# TdsReworkfullSMD.net
KiCad netlist of a schematic drawn in EAGLE
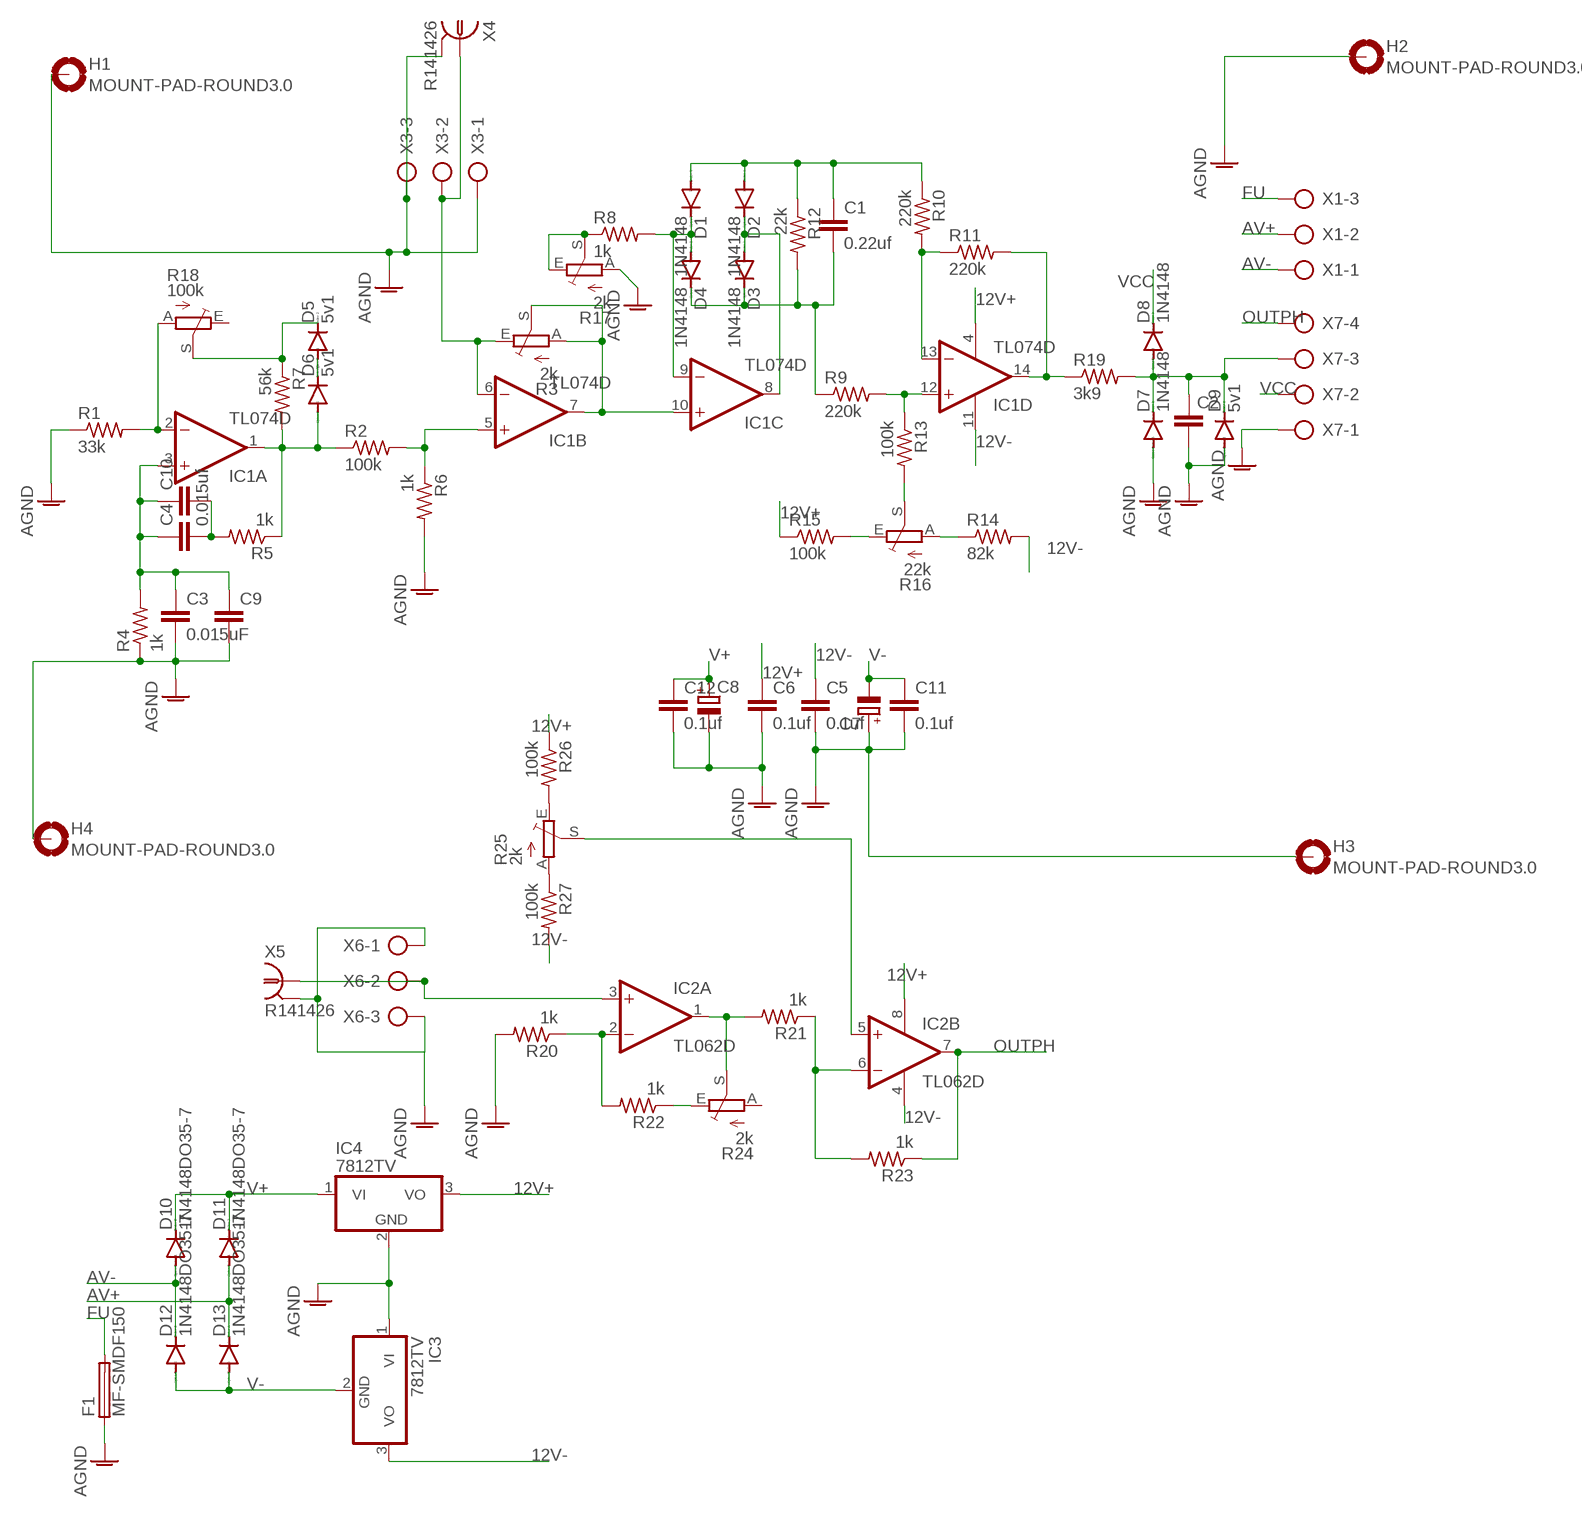
[diagram p0: schematic, sheet 1]

(export (version "E")
  (design (tool "Eeschema 10.0.6"))
  (components
    (comp (ref "C1")
      (value "0.22uf")
      (footprint "eagle-import:C0805")
      (libsource (lib "eagle-import") (part "C-EUC0805"))
    )
    (comp (ref "C2")
      (value "C-EUC0805")
      (footprint "eagle-import:C0805")
      (libsource (lib "eagle-import") (part "C-EUC0805"))
    )
    (comp (ref "C3")
      (value "0.015uF")
      (footprint "eagle-import:C050-024X044")
      (libsource (lib "eagle-import") (part "C-EU050-024X044"))
    )
    (comp (ref "C4")
      (value "0.015uf")
      (footprint "eagle-import:C050-024X044")
      (libsource (lib "eagle-import") (part "C-EU050-024X044"))
    )
    (comp (ref "C5")
      (value "0.1uf")
      (footprint "eagle-import:C0805")
      (libsource (lib "eagle-import") (part "C-EUC0805"))
    )
    (comp (ref "C6")
      (value "0.1uf")
      (footprint "eagle-import:C0805")
      (libsource (lib "eagle-import") (part "C-EUC0805"))
    )
    (comp (ref "C7")
      (value "CPOL-EUE5-8.5")
      (footprint "eagle-import:E5-8,5")
      (libsource (lib "eagle-import") (part "CPOL-EUE5-8.5"))
    )
    (comp (ref "C8")
      (value "CPOL-EUE5-8.5")
      (footprint "eagle-import:E5-8,5")
      (libsource (lib "eagle-import") (part "CPOL-EUE5-8.5"))
    )
    (comp (ref "C9")
      (value "C-EUC0805")
      (footprint "eagle-import:C0805")
      (libsource (lib "eagle-import") (part "C-EUC0805"))
    )
    (comp (ref "C10")
      (value "C-EUC0805")
      (footprint "eagle-import:C0805")
      (libsource (lib "eagle-import") (part "C-EUC0805"))
    )
    (comp (ref "C11")
      (value "0.1uf")
      (footprint "eagle-import:C0805")
      (libsource (lib "eagle-import") (part "C-EUC0805"))
    )
    (comp (ref "C12")
      (value "0.1uf")
      (footprint "eagle-import:C0805")
      (libsource (lib "eagle-import") (part "C-EUC0805"))
    )
    (comp (ref "D1")
      (value "1N4148")
      (footprint "eagle-import:DO35-7")
      (libsource (lib "eagle-import") (part "1N4148DO35-7"))
    )
    (comp (ref "D2")
      (value "1N4148")
      (footprint "eagle-import:DO35-7")
      (libsource (lib "eagle-import") (part "1N4148DO35-7"))
    )
    (comp (ref "D3")
      (value "1N4148")
      (footprint "eagle-import:DO35-7")
      (libsource (lib "eagle-import") (part "1N4148DO35-7"))
    )
    (comp (ref "D4")
      (value "1N4148")
      (footprint "eagle-import:DO35-7")
      (libsource (lib "eagle-import") (part "1N4148DO35-7"))
    )
    (comp (ref "D5")
      (value "5v1")
      (footprint "eagle-import:DO35-7")
      (libsource (lib "eagle-import") (part "1N4148DO35-7"))
    )
    (comp (ref "D6")
      (value "5v1")
      (footprint "eagle-import:DO35-7")
      (libsource (lib "eagle-import") (part "1N4148DO35-7"))
    )
    (comp (ref "D7")
      (value "1N4148")
      (footprint "eagle-import:DO35-7")
      (libsource (lib "eagle-import") (part "1N4148DO35-7"))
    )
    (comp (ref "D8")
      (value "1N4148")
      (footprint "eagle-import:DO35-7")
      (libsource (lib "eagle-import") (part "1N4148DO35-7"))
    )
    (comp (ref "D9")
      (value "5v1")
      (footprint "eagle-import:DO35-7")
      (libsource (lib "eagle-import") (part "1N4148DO35-7"))
    )
    (comp (ref "D10")
      (value "1N4148DO35-7")
      (footprint "eagle-import:DO35-7")
      (libsource (lib "eagle-import") (part "1N4148DO35-7"))
    )
    (comp (ref "D11")
      (value "1N4148DO35-7")
      (footprint "eagle-import:DO35-7")
      (libsource (lib "eagle-import") (part "1N4148DO35-7"))
    )
    (comp (ref "D12")
      (value "1N4148DO35-7")
      (footprint "eagle-import:DO35-7")
      (libsource (lib "eagle-import") (part "1N4148DO35-7"))
    )
    (comp (ref "D13")
      (value "1N4148DO35-7")
      (footprint "eagle-import:DO35-7")
      (libsource (lib "eagle-import") (part "1N4148DO35-7"))
    )
    (comp (ref "F1")
      (value "MF-SMDF150")
      (footprint "eagle-import:MF-SMDF050")
      (libsource (lib "eagle-import") (part "MF-SMDF150"))
    )
    (comp (ref "H1")
      (value "MOUNT-PAD-ROUND3.0")
      (footprint "eagle-import:3,0-PAD")
      (libsource (lib "eagle-import") (part "MOUNT-PAD-ROUND3.0"))
    )
    (comp (ref "H2")
      (value "MOUNT-PAD-ROUND3.0")
      (footprint "eagle-import:3,0-PAD")
      (libsource (lib "eagle-import") (part "MOUNT-PAD-ROUND3.0"))
    )
    (comp (ref "H3")
      (value "MOUNT-PAD-ROUND3.0")
      (footprint "eagle-import:3,0-PAD")
      (libsource (lib "eagle-import") (part "MOUNT-PAD-ROUND3.0"))
    )
    (comp (ref "H4")
      (value "MOUNT-PAD-ROUND3.0")
      (footprint "eagle-import:3,0-PAD")
      (libsource (lib "eagle-import") (part "MOUNT-PAD-ROUND3.0"))
    )
    (comp (ref "IC1")
      (value "TL074D")
      (footprint "eagle-import:SO14")
      (libsource (lib "eagle-import") (part "TL074D"))
    )
    (comp (ref "IC2")
      (value "TL062D")
      (footprint "eagle-import:SO08")
      (libsource (lib "eagle-import") (part "TL062D"))
    )
    (comp (ref "IC3")
      (value "7812TV")
      (footprint "eagle-import:TO220V")
      (libsource (lib "eagle-import") (part "78TV12"))
    )
    (comp (ref "IC4")
      (value "7812TV")
      (footprint "eagle-import:TO220V")
      (libsource (lib "eagle-import") (part "78TV12"))
    )
    (comp (ref "R1")
      (value "33k")
      (footprint "eagle-import:R0805")
      (libsource (lib "eagle-import") (part "R-US_R0805"))
    )
    (comp (ref "R2")
      (value "100k")
      (footprint "eagle-import:R0805")
      (libsource (lib "eagle-import") (part "R-US_R0805"))
    )
    (comp (ref "R3")
      (value "2k")
      (footprint "eagle-import:S64W")
      (libsource (lib "eagle-import") (part "TRIM_EU-S64W"))
    )
    (comp (ref "R4")
      (value "1k")
      (footprint "eagle-import:R0805")
      (libsource (lib "eagle-import") (part "R-US_R0805"))
    )
    (comp (ref "R5")
      (value "1k")
      (footprint "eagle-import:R0805")
      (libsource (lib "eagle-import") (part "R-US_R0805"))
    )
    (comp (ref "R6")
      (value "1k")
      (footprint "eagle-import:R0805")
      (libsource (lib "eagle-import") (part "R-US_R0805"))
    )
    (comp (ref "R7")
      (value "56k")
      (footprint "eagle-import:R0805")
      (libsource (lib "eagle-import") (part "R-US_R0805"))
    )
    (comp (ref "R8")
      (value "1k")
      (footprint "eagle-import:R0805")
      (libsource (lib "eagle-import") (part "R-US_R0805"))
    )
    (comp (ref "R9")
      (value "220k")
      (footprint "eagle-import:R0805")
      (libsource (lib "eagle-import") (part "R-US_R0805"))
    )
    (comp (ref "R10")
      (value "220k")
      (footprint "eagle-import:R0805")
      (libsource (lib "eagle-import") (part "R-US_R0805"))
    )
    (comp (ref "R11")
      (value "220k")
      (footprint "eagle-import:R0805")
      (libsource (lib "eagle-import") (part "R-US_R0805"))
    )
    (comp (ref "R12")
      (value "22k")
      (footprint "eagle-import:R0805")
      (libsource (lib "eagle-import") (part "R-US_R0805"))
    )
    (comp (ref "R13")
      (value "100k")
      (footprint "eagle-import:R0805")
      (libsource (lib "eagle-import") (part "R-US_R0805"))
    )
    (comp (ref "R14")
      (value "82k")
      (footprint "eagle-import:R0805")
      (libsource (lib "eagle-import") (part "R-US_R0805"))
    )
    (comp (ref "R15")
      (value "100k")
      (footprint "eagle-import:R0805")
      (libsource (lib "eagle-import") (part "R-US_R0805"))
    )
    (comp (ref "R16")
      (value "22k")
      (footprint "eagle-import:S64W")
      (libsource (lib "eagle-import") (part "TRIM_EU-S64W"))
    )
    (comp (ref "R17")
      (value "2k")
      (footprint "eagle-import:S64W")
      (libsource (lib "eagle-import") (part "TRIM_EU-S64W"))
    )
    (comp (ref "R18")
      (value "100k")
      (footprint "eagle-import:S64W")
      (libsource (lib "eagle-import") (part "TRIM_EU-S64W"))
    )
    (comp (ref "R19")
      (value "3k9")
      (footprint "eagle-import:R0805")
      (libsource (lib "eagle-import") (part "R-US_R0805"))
    )
    (comp (ref "R20")
      (value "1k")
      (footprint "eagle-import:R0805")
      (libsource (lib "eagle-import") (part "R-US_R0805"))
    )
    (comp (ref "R21")
      (value "1k")
      (footprint "eagle-import:R0805")
      (libsource (lib "eagle-import") (part "R-US_R0805"))
    )
    (comp (ref "R22")
      (value "1k")
      (footprint "eagle-import:R0805")
      (libsource (lib "eagle-import") (part "R-US_R0805"))
    )
    (comp (ref "R23")
      (value "1k")
      (footprint "eagle-import:R0805")
      (libsource (lib "eagle-import") (part "R-US_R0805"))
    )
    (comp (ref "R24")
      (value "2k")
      (footprint "eagle-import:S64W")
      (libsource (lib "eagle-import") (part "TRIM_EU-S64W"))
    )
    (comp (ref "R25")
      (value "2k")
      (footprint "eagle-import:S64W")
      (libsource (lib "eagle-import") (part "TRIM_EU-S64W"))
    )
    (comp (ref "R26")
      (value "100k")
      (footprint "eagle-import:R0805")
      (libsource (lib "eagle-import") (part "R-US_R0805"))
    )
    (comp (ref "R27")
      (value "100k")
      (footprint "eagle-import:R0805")
      (libsource (lib "eagle-import") (part "R-US_R0805"))
    )
    (comp (ref "X1")
      (value "AK500/3")
      (footprint "eagle-import:AK500_3")
      (libsource (lib "eagle-import") (part "AK500/3"))
    )
    (comp (ref "X3")
      (value "AK500/3")
      (footprint "eagle-import:AK500_3")
      (libsource (lib "eagle-import") (part "AK500/3"))
    )
    (comp (ref "X4")
      (value "R141426")
      (footprint "eagle-import:R141426")
      (fields (field (name "MF") "FARNELL") (field (name "MPN") "R141426161"))
      (libsource (lib "eagle-import") (part "R141426"))
    )
    (comp (ref "X5")
      (value "R141426")
      (footprint "eagle-import:R141426")
      (fields (field (name "MF") "FARNELL") (field (name "MPN") "R141426161"))
      (libsource (lib "eagle-import") (part "R141426"))
    )
    (comp (ref "X6")
      (value "AK500/3")
      (footprint "eagle-import:AK500_3")
      (libsource (lib "eagle-import") (part "AK500/3"))
    )
    (comp (ref "X7")
      (value "AK500/4")
      (footprint "eagle-import:AK500_4")
      (libsource (lib "eagle-import") (part "AK500/4"))
    )
  )
  (nets
    (net (code "1") (name "/12V+") (class "Default")
      (node (ref "C6") (pin "1") (pinfunction "1_1") (pintype "passive"))
      (node (ref "IC1") (pin "4") (pinfunction "V+_4") (pintype "power_in"))
      (node (ref "IC2") (pin "8") (pinfunction "V+_8") (pintype "power_in"))
      (node (ref "IC4") (pin "3") (pinfunction "VO_3") (pintype "passive"))
      (node (ref "R15") (pin "1") (pinfunction "1_1") (pintype "passive"))
      (node (ref "R26") (pin "1") (pinfunction "1_1") (pintype "passive"))
    )
    (net (code "2") (name "/12V-") (class "Default")
      (node (ref "C5") (pin "1") (pinfunction "1_1") (pintype "passive"))
      (node (ref "IC1") (pin "11") (pinfunction "V-_11") (pintype "power_in"))
      (node (ref "IC2") (pin "4") (pinfunction "V-_4") (pintype "power_in"))
      (node (ref "IC3") (pin "3") (pinfunction "VO_3") (pintype "passive"))
      (node (ref "R14") (pin "2") (pinfunction "2_2") (pintype "passive"))
      (node (ref "R27") (pin "2") (pinfunction "2_2") (pintype "passive"))
    )
    (net (code "3") (name "/AV+") (class "Default")
      (node (ref "D11") (pin "A") (pinfunction "A_A") (pintype "passive"))
      (node (ref "D13") (pin "C") (pinfunction "C_C") (pintype "passive"))
      (node (ref "X1") (pin "2") (pinfunction "KL_2") (pintype "passive"))
    )
    (net (code "4") (name "/AV-") (class "Default")
      (node (ref "D10") (pin "A") (pinfunction "A_A") (pintype "passive"))
      (node (ref "D12") (pin "C") (pinfunction "C_C") (pintype "passive"))
      (node (ref "X1") (pin "1") (pinfunction "KL_1") (pintype "passive"))
    )
    (net (code "5") (name "/FU") (class "Default")
      (node (ref "F1") (pin "2") (pinfunction "2_2") (pintype "passive"))
      (node (ref "X1") (pin "3") (pinfunction "KL_3") (pintype "passive"))
    )
    (net (code "6") (name "/OUTPH") (class "Default")
      (node (ref "IC2") (pin "7") (pinfunction "OUT_7") (pintype "output"))
      (node (ref "R23") (pin "1") (pinfunction "1_1") (pintype "passive"))
      (node (ref "X7") (pin "4") (pinfunction "KL_4") (pintype "passive"))
    )
    (net (code "7") (name "/V+") (class "Default")
      (node (ref "C12") (pin "1") (pinfunction "1_1") (pintype "passive"))
      (node (ref "C8") (pin "+") (pinfunction "+_+") (pintype "passive"))
      (node (ref "D10") (pin "C") (pinfunction "C_C") (pintype "passive"))
      (node (ref "D11") (pin "C") (pinfunction "C_C") (pintype "passive"))
      (node (ref "IC4") (pin "1") (pinfunction "VI_1") (pintype "input"))
    )
    (net (code "8") (name "/V-") (class "Default")
      (node (ref "C11") (pin "1") (pinfunction "1_1") (pintype "passive"))
      (node (ref "C7") (pin "-") (pinfunction "-_-") (pintype "passive"))
      (node (ref "D12") (pin "A") (pinfunction "A_A") (pintype "passive"))
      (node (ref "D13") (pin "A") (pinfunction "A_A") (pintype "passive"))
      (node (ref "IC3") (pin "2") (pinfunction "GND_2") (pintype "passive"))
    )
    (net (code "9") (name "/VCC") (class "Default")
      (node (ref "D8") (pin "C") (pinfunction "C_C") (pintype "passive"))
      (node (ref "X7") (pin "2") (pinfunction "KL_2") (pintype "passive"))
    )
    (net (code "10") (name "AGND") (class "Default")
      (node (ref "C11") (pin "2") (pinfunction "2_2") (pintype "passive"))
      (node (ref "C12") (pin "2") (pinfunction "2_2") (pintype "passive"))
      (node (ref "C2") (pin "2") (pinfunction "2_2") (pintype "passive"))
      (node (ref "C3") (pin "2") (pinfunction "2_2") (pintype "passive"))
      (node (ref "C5") (pin "2") (pinfunction "2_2") (pintype "passive"))
      (node (ref "C6") (pin "2") (pinfunction "2_2") (pintype "passive"))
      (node (ref "C7") (pin "+") (pinfunction "+_+") (pintype "passive"))
      (node (ref "C8") (pin "-") (pinfunction "-_-") (pintype "passive"))
      (node (ref "C9") (pin "2") (pinfunction "2_2") (pintype "passive"))
      (node (ref "D7") (pin "A") (pinfunction "A_A") (pintype "passive"))
      (node (ref "D9") (pin "A") (pinfunction "A_A") (pintype "passive"))
      (node (ref "F1") (pin "1") (pinfunction "1_1") (pintype "passive"))
      (node (ref "H1") (pin "B3,0") (pinfunction "MOUNT_B3,0") (pintype "passive"))
      (node (ref "H2") (pin "B3,0") (pinfunction "MOUNT_B3,0") (pintype "passive"))
      (node (ref "H3") (pin "B3,0") (pinfunction "MOUNT_B3,0") (pintype "passive"))
      (node (ref "H4") (pin "B3,0") (pinfunction "MOUNT_B3,0") (pintype "passive"))
      (node (ref "IC3") (pin "1") (pinfunction "VI_1") (pintype "input"))
      (node (ref "IC4") (pin "2") (pinfunction "GND_2") (pintype "passive"))
      (node (ref "R1") (pin "1") (pinfunction "1_1") (pintype "passive"))
      (node (ref "R17") (pin "A") (pinfunction "A_A") (pintype "passive"))
      (node (ref "R20") (pin "2") (pinfunction "2_2") (pintype "passive"))
      (node (ref "R4") (pin "1") (pinfunction "1_1") (pintype "passive"))
      (node (ref "R6") (pin "2") (pinfunction "2_2") (pintype "passive"))
      (node (ref "X3") (pin "1") (pinfunction "KL_1") (pintype "passive"))
      (node (ref "X3") (pin "3") (pinfunction "KL_3") (pintype "passive"))
      (node (ref "X4") (pin "2") (pinfunction "2_2") (pintype "passive"))
      (node (ref "X4") (pin "3") (pinfunction "2_3") (pintype "passive"))
      (node (ref "X4") (pin "4") (pinfunction "2_4") (pintype "passive"))
      (node (ref "X4") (pin "5") (pinfunction "2_5") (pintype "passive"))
      (node (ref "X5") (pin "2") (pinfunction "2_2") (pintype "passive"))
      (node (ref "X5") (pin "3") (pinfunction "2_3") (pintype "passive"))
      (node (ref "X5") (pin "4") (pinfunction "2_4") (pintype "passive"))
      (node (ref "X5") (pin "5") (pinfunction "2_5") (pintype "passive"))
      (node (ref "X6") (pin "1") (pinfunction "KL_1") (pintype "passive"))
      (node (ref "X6") (pin "3") (pinfunction "KL_3") (pintype "passive"))
      (node (ref "X7") (pin "1") (pinfunction "KL_1") (pintype "passive"))
    )
    (net (code "11") (name "Net-(C1-Pad1)") (class "Default")
      (node (ref "C1") (pin "1") (pinfunction "1_1") (pintype "passive"))
      (node (ref "D1") (pin "A") (pinfunction "A_A") (pintype "passive"))
      (node (ref "D2") (pin "A") (pinfunction "A_A") (pintype "passive"))
      (node (ref "R10") (pin "1") (pinfunction "1_1") (pintype "passive"))
      (node (ref "R12") (pin "1") (pinfunction "1_1") (pintype "passive"))
    )
    (net (code "12") (name "Net-(C1-Pad2)") (class "Default")
      (node (ref "C1") (pin "2") (pinfunction "2_2") (pintype "passive"))
      (node (ref "D3") (pin "C") (pinfunction "C_C") (pintype "passive"))
      (node (ref "D4") (pin "C") (pinfunction "C_C") (pintype "passive"))
      (node (ref "R12") (pin "2") (pinfunction "2_2") (pintype "passive"))
      (node (ref "R9") (pin "1") (pinfunction "1_1") (pintype "passive"))
    )
    (net (code "13") (name "Net-(C10-Pad2)") (class "Default")
      (node (ref "C10") (pin "2") (pinfunction "2_2") (pintype "passive"))
      (node (ref "C4") (pin "2") (pinfunction "2_2") (pintype "passive"))
      (node (ref "R5") (pin "2") (pinfunction "2_2") (pintype "passive"))
    )
    (net (code "14") (name "Net-(D5-PadA)") (class "Default")
      (node (ref "D5") (pin "A") (pinfunction "A_A") (pintype "passive"))
      (node (ref "D6") (pin "C") (pinfunction "C_C") (pintype "passive"))
    )
    (net (code "15") (name "Net-(D5-PadC)") (class "Default")
      (node (ref "D5") (pin "C") (pinfunction "C_C") (pintype "passive"))
      (node (ref "R18") (pin "S") (pinfunction "S_S") (pintype "passive"))
      (node (ref "R7") (pin "1") (pinfunction "1_1") (pintype "passive"))
    )
    (net (code "16") (name "Net-(IC1A-+IN)") (class "Default")
      (node (ref "C10") (pin "1") (pinfunction "1_1") (pintype "passive"))
      (node (ref "C3") (pin "1") (pinfunction "1_1") (pintype "passive"))
      (node (ref "C4") (pin "1") (pinfunction "1_1") (pintype "passive"))
      (node (ref "C9") (pin "1") (pinfunction "1_1") (pintype "passive"))
      (node (ref "IC1") (pin "3") (pinfunction "+IN_3") (pintype "input"))
      (node (ref "R4") (pin "2") (pinfunction "2_2") (pintype "passive"))
    )
    (net (code "17") (name "Net-(IC1A--IN)") (class "Default")
      (node (ref "IC1") (pin "2") (pinfunction "-IN_2") (pintype "input"))
      (node (ref "R1") (pin "2") (pinfunction "2_2") (pintype "passive"))
      (node (ref "R18") (pin "A") (pinfunction "A_A") (pintype "passive"))
    )
    (net (code "18") (name "Net-(IC1A-OUT)") (class "Default")
      (node (ref "D6") (pin "A") (pinfunction "A_A") (pintype "passive"))
      (node (ref "IC1") (pin "1") (pinfunction "OUT_1") (pintype "output"))
      (node (ref "R2") (pin "1") (pinfunction "1_1") (pintype "passive"))
      (node (ref "R5") (pin "1") (pinfunction "1_1") (pintype "passive"))
      (node (ref "R7") (pin "2") (pinfunction "2_2") (pintype "passive"))
    )
    (net (code "19") (name "Net-(IC1B-+IN)") (class "Default")
      (node (ref "IC1") (pin "5") (pinfunction "+IN_5") (pintype "input"))
      (node (ref "R2") (pin "2") (pinfunction "2_2") (pintype "passive"))
      (node (ref "R6") (pin "1") (pinfunction "1_1") (pintype "passive"))
    )
    (net (code "20") (name "Net-(IC1B--IN)") (class "Default")
      (node (ref "IC1") (pin "6") (pinfunction "-IN_6") (pintype "input"))
      (node (ref "R3") (pin "E") (pinfunction "E_E") (pintype "passive"))
      (node (ref "X3") (pin "2") (pinfunction "KL_2") (pintype "passive"))
      (node (ref "X4") (pin "1") (pinfunction "1_1") (pintype "passive"))
    )
    (net (code "21") (name "Net-(IC1B-OUT)") (class "Default")
      (node (ref "IC1") (pin "10") (pinfunction "+IN_10") (pintype "input"))
      (node (ref "IC1") (pin "7") (pinfunction "OUT_7") (pintype "output"))
      (node (ref "R3") (pin "A") (pinfunction "A_A") (pintype "passive"))
      (node (ref "R3") (pin "S") (pinfunction "S_S") (pintype "passive"))
    )
    (net (code "22") (name "Net-(IC1C--IN)") (class "Default")
      (node (ref "D1") (pin "C") (pinfunction "C_C") (pintype "passive"))
      (node (ref "D4") (pin "A") (pinfunction "A_A") (pintype "passive"))
      (node (ref "IC1") (pin "9") (pinfunction "-IN_9") (pintype "input"))
      (node (ref "R8") (pin "2") (pinfunction "2_2") (pintype "passive"))
    )
    (net (code "23") (name "Net-(IC1C-OUT)") (class "Default")
      (node (ref "D2") (pin "C") (pinfunction "C_C") (pintype "passive"))
      (node (ref "D3") (pin "A") (pinfunction "A_A") (pintype "passive"))
      (node (ref "IC1") (pin "8") (pinfunction "OUT_8") (pintype "output"))
    )
    (net (code "24") (name "Net-(IC1D-+IN)") (class "Default")
      (node (ref "IC1") (pin "12") (pinfunction "+IN_12") (pintype "input"))
      (node (ref "R13") (pin "1") (pinfunction "1_1") (pintype "passive"))
      (node (ref "R9") (pin "2") (pinfunction "2_2") (pintype "passive"))
    )
    (net (code "25") (name "Net-(IC1D--IN)") (class "Default")
      (node (ref "IC1") (pin "13") (pinfunction "-IN_13") (pintype "input"))
      (node (ref "R10") (pin "2") (pinfunction "2_2") (pintype "passive"))
      (node (ref "R11") (pin "1") (pinfunction "1_1") (pintype "passive"))
    )
    (net (code "26") (name "Net-(IC1D-OUT)") (class "Default")
      (node (ref "IC1") (pin "14") (pinfunction "OUT_14") (pintype "output"))
      (node (ref "R11") (pin "2") (pinfunction "2_2") (pintype "passive"))
      (node (ref "R19") (pin "1") (pinfunction "1_1") (pintype "passive"))
    )
    (net (code "27") (name "Net-(IC2A-+IN)") (class "Default")
      (node (ref "IC2") (pin "3") (pinfunction "+IN_3") (pintype "input"))
      (node (ref "X5") (pin "1") (pinfunction "1_1") (pintype "passive"))
      (node (ref "X6") (pin "2") (pinfunction "KL_2") (pintype "passive"))
    )
    (net (code "28") (name "Net-(IC2A--IN)") (class "Default")
      (node (ref "IC2") (pin "2") (pinfunction "-IN_2") (pintype "input"))
      (node (ref "R20") (pin "1") (pinfunction "1_1") (pintype "passive"))
      (node (ref "R22") (pin "2") (pinfunction "2_2") (pintype "passive"))
    )
    (net (code "29") (name "Net-(IC2A-OUT)") (class "Default")
      (node (ref "IC2") (pin "1") (pinfunction "OUT_1") (pintype "output"))
      (node (ref "R21") (pin "2") (pinfunction "2_2") (pintype "passive"))
      (node (ref "R24") (pin "S") (pinfunction "S_S") (pintype "passive"))
    )
    (net (code "30") (name "Net-(IC2B-+IN)") (class "Default")
      (node (ref "IC2") (pin "5") (pinfunction "+IN_5") (pintype "input"))
      (node (ref "R25") (pin "S") (pinfunction "S_S") (pintype "passive"))
    )
    (net (code "31") (name "Net-(IC2B--IN)") (class "Default")
      (node (ref "IC2") (pin "6") (pinfunction "-IN_6") (pintype "input"))
      (node (ref "R21") (pin "1") (pinfunction "1_1") (pintype "passive"))
      (node (ref "R23") (pin "2") (pinfunction "2_2") (pintype "passive"))
    )
    (net (code "32") (name "Net-(R13-Pad2)") (class "Default")
      (node (ref "R13") (pin "2") (pinfunction "2_2") (pintype "passive"))
      (node (ref "R16") (pin "S") (pinfunction "S_S") (pintype "passive"))
    )
    (net (code "33") (name "Net-(R14-Pad1)") (class "Default")
      (node (ref "R14") (pin "1") (pinfunction "1_1") (pintype "passive"))
      (node (ref "R16") (pin "A") (pinfunction "A_A") (pintype "passive"))
    )
    (net (code "34") (name "Net-(R15-Pad2)") (class "Default")
      (node (ref "R15") (pin "2") (pinfunction "2_2") (pintype "passive"))
      (node (ref "R16") (pin "E") (pinfunction "E_E") (pintype "passive"))
    )
    (net (code "35") (name "Net-(R17-PadE)") (class "Default")
      (node (ref "R17") (pin "E") (pinfunction "E_E") (pintype "passive"))
      (node (ref "R17") (pin "S") (pinfunction "S_S") (pintype "passive"))
      (node (ref "R8") (pin "1") (pinfunction "1_1") (pintype "passive"))
    )
    (net (code "36") (name "Net-(R22-Pad1)") (class "Default")
      (node (ref "R22") (pin "1") (pinfunction "1_1") (pintype "passive"))
      (node (ref "R24") (pin "E") (pinfunction "E_E") (pintype "passive"))
    )
    (net (code "37") (name "Net-(R25-PadA)") (class "Default")
      (node (ref "R25") (pin "A") (pinfunction "A_A") (pintype "passive"))
      (node (ref "R27") (pin "1") (pinfunction "1_1") (pintype "passive"))
    )
    (net (code "38") (name "Net-(R25-PadE)") (class "Default")
      (node (ref "R25") (pin "E") (pinfunction "E_E") (pintype "passive"))
      (node (ref "R26") (pin "2") (pinfunction "2_2") (pintype "passive"))
    )
    (net (code "39") (name "Net-(X7C-KL)") (class "Default")
      (node (ref "C2") (pin "1") (pinfunction "1_1") (pintype "passive"))
      (node (ref "D7") (pin "C") (pinfunction "C_C") (pintype "passive"))
      (node (ref "D8") (pin "A") (pinfunction "A_A") (pintype "passive"))
      (node (ref "D9") (pin "C") (pinfunction "C_C") (pintype "passive"))
      (node (ref "R19") (pin "2") (pinfunction "2_2") (pintype "passive"))
      (node (ref "X7") (pin "3") (pinfunction "KL_3") (pintype "passive"))
    )
    (net (code "40") (name "unconnected-(R18-PadE)") (class "Default")
      (node (ref "R18") (pin "E") (pinfunction "E_E") (pintype "passive"))
    )
    (net (code "41") (name "unconnected-(R24-PadA)") (class "Default")
      (node (ref "R24") (pin "A") (pinfunction "A_A") (pintype "passive"))
    )
  )
)
